# 1_P1_schdoc.net
KiCad netlist of a schematic drawn in Altium Designer
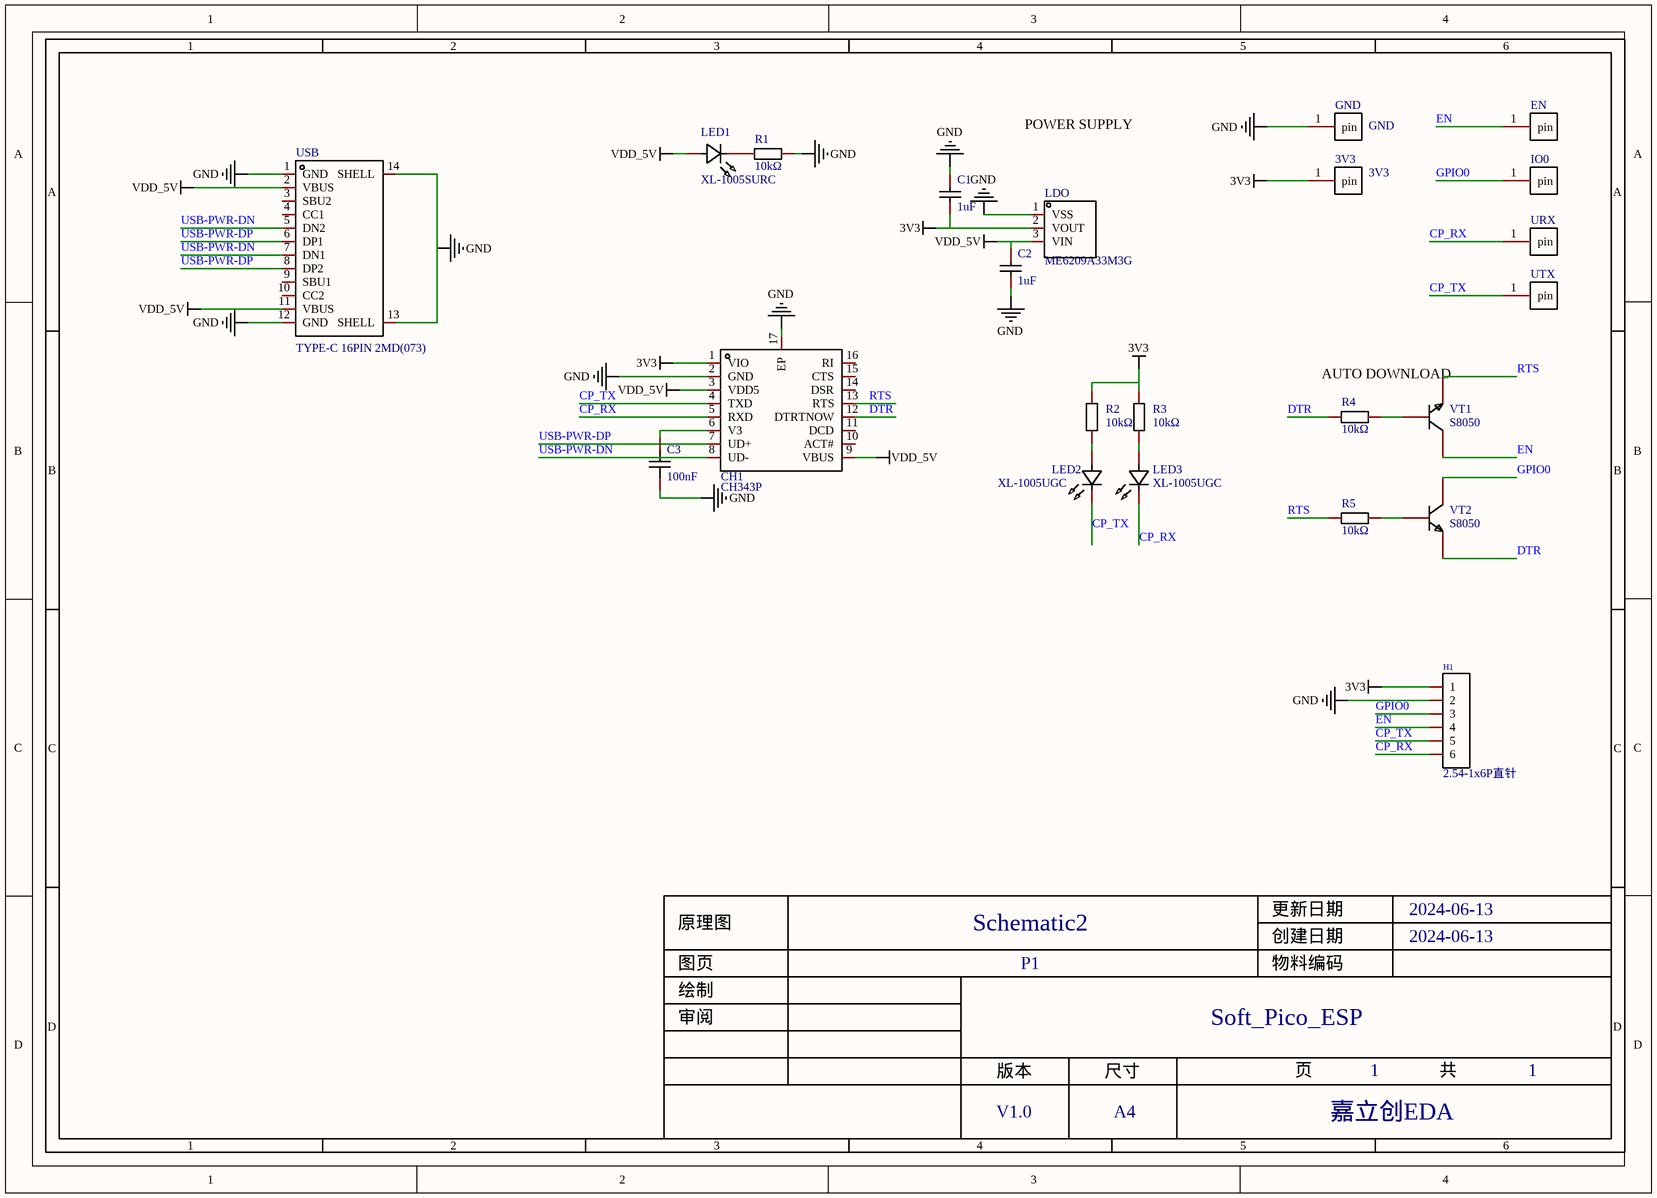
[diagram p0: 1_P1.schdoc.schdoc]

(export (version "E")
  (design (tool "Eeschema 10.0.6"))
  (components
    (comp (ref "3V3")
      (value "3V3")
      (fields (field (name "NAME") "3V3"))
      (libsource (lib "altium-import") (part "root_0_FPCB焊脚_"))
    )
    (comp (ref "C1")
      (value "1uF")
      (fields
        (field (name "MANUFACTURER") "SAMSUNG(三星)")
        (field (name "MANUFACTURER PART") "CL05A105KP5NNNC")
        (field (name "TOLERANCE") "±10%")
      )
      (libsource (lib "altium-import") (part "root_1_CL05A105KP5NNNC_"))
    )
    (comp (ref "C2")
      (value "1uF")
      (fields
        (field (name "MANUFACTURER") "SAMSUNG(三星)")
        (field (name "MANUFACTURER PART") "CL05A105KP5NNNC")
        (field (name "TOLERANCE") "±10%")
      )
      (libsource (lib "altium-import") (part "root_1_CL05A105KP5NNNC_"))
    )
    (comp (ref "C3")
      (value "100nF")
      (fields
        (field (name "MANUFACTURER") "YAGEO(国巨)")
        (field (name "MANUFACTURER PART") "CC0402KRX7R7BB104")
        (field (name "TOLERANCE") "±10%")
      )
      (libsource (lib "altium-import") (part "root_1_CC0402KRX7R7BB104_"))
    )
    (comp (ref "CH1")
      (value "CH343P")
      (description "应用功能:-;接口协议:-;")
      (fields (field (name "NAME") "CH343P") (field (name "MANUFACTURER") "WCH(南京沁恒)"))
      (libsource (lib "altium-import") (part "root_0_CH343P_"))
    )
    (comp (ref "EN") (value "FPCB焊脚") (libsource (lib "altium-import") (part "root_0_FPCB焊脚_")))
    (comp (ref "GND")
      (value "GND")
      (fields (field (name "NAME") "GND"))
      (libsource (lib "altium-import") (part "root_0_FPCB焊脚_"))
    )
    (comp (ref "H1")
      (value "2.54-1x6P直针")
      (fields (field (name "NAME") "2.54-1x6P直针") (field (name "MANUFACTURER") "BOOMELE(博穆精密)"))
      (libsource (lib "altium-import") (part "root_0_2.54-1x6P直针_"))
    )
    (comp (ref "IO0") (value "FPCB焊脚") (libsource (lib "altium-import") (part "root_0_FPCB焊脚_")))
    (comp (ref "LDO")
      (value "ME6209A33M3G")
      (description "输出类型:固定;最大输入电压:18V;输出电压:3.3V;最大输出电流:250mA;电源纹波抑制比(PSRR):-;输出极性:正极;")
      (fields (field (name "NAME") "ME6209A33M3G") (field (name "MANUFACTURER") "MICRONE(南京微盟)"))
      (libsource (lib "altium-import") (part "root_0_ME6209A33M3G_"))
    )
    (comp (ref "LED1")
      (value "XL-1005SURC")
      (description "发光颜色:红色;功率:55mW;正向电流:25mA;主波长:620nm;透镜颜色:无色透明透镜;色温:6000K~7000K;发光角度:120°;载带方式:正贴;工作温度:-30℃~+85℃;")
      (fields (field (name "NAME") "XL-1005SURC") (field (name "MANUFACTURER") "XINGLIGHT(成兴光)"))
      (libsource (lib "altium-import") (part "root_2_XL-1005SURC_"))
    )
    (comp (ref "LED2")
      (value "XL-1005UGC")
      (description "发光颜色:翠绿色;功率:80mW;正向电流:25mA;主波长:516nm;透镜颜色:无色透明透镜;色温:-;发光角度:120°;载带方式:正贴;工作温度:-30℃~+85℃;")
      (fields (field (name "NAME") "XL-1005UGC") (field (name "MANUFACTURER") "XINGLIGHT(成兴光)"))
      (libsource (lib "altium-import") (part "root_1_XL-1005UGC_"))
    )
    (comp (ref "LED3")
      (value "XL-1005UGC")
      (description "发光颜色:翠绿色;功率:80mW;正向电流:25mA;主波长:516nm;透镜颜色:无色透明透镜;色温:-;发光角度:120°;载带方式:正贴;工作温度:-30℃~+85℃;")
      (fields (field (name "NAME") "XL-1005UGC") (field (name "MANUFACTURER") "XINGLIGHT(成兴光)"))
      (libsource (lib "altium-import") (part "root_1_XL-1005UGC_"))
    )
    (comp (ref "R1")
      (value "10kΩ")
      (description "电阻类型:薄膜电阻;阻值:10kΩ;精度:±0.5%;功率:63mW;温度系数:±25ppm/;最大工作电压:25V;工作温度范围:-55~+155;")
      (fields
        (field (name "MANUFACTURER") "EVER OHMS(天二科技)")
        (field (name "MANUFACTURER PART") "TR0402D10K0Q1025Z")
      )
      (libsource (lib "altium-import") (part "root_2_TR0402D10K0Q1025Z_"))
    )
    (comp (ref "R2")
      (value "10kΩ")
      (description "电阻类型:薄膜电阻;阻值:10kΩ;精度:±0.5%;功率:63mW;温度系数:±25ppm/;最大工作电压:25V;工作温度范围:-55~+155;")
      (fields
        (field (name "MANUFACTURER") "EVER OHMS(天二科技)")
        (field (name "MANUFACTURER PART") "TR0402D10K0Q1025Z")
      )
      (libsource (lib "altium-import") (part "root_3_TR0402D10K0Q1025Z_"))
    )
    (comp (ref "R3")
      (value "10kΩ")
      (description "电阻类型:薄膜电阻;阻值:10kΩ;精度:±0.5%;功率:63mW;温度系数:±25ppm/;最大工作电压:25V;工作温度范围:-55~+155;")
      (fields
        (field (name "MANUFACTURER") "EVER OHMS(天二科技)")
        (field (name "MANUFACTURER PART") "TR0402D10K0Q1025Z")
      )
      (libsource (lib "altium-import") (part "root_3_TR0402D10K0Q1025Z_"))
    )
    (comp (ref "R4")
      (value "10kΩ")
      (description "电阻类型:薄膜电阻;阻值:10kΩ;精度:±0.5%;功率:63mW;温度系数:±25ppm/;最大工作电压:25V;工作温度范围:-55~+155;")
      (fields
        (field (name "MANUFACTURER") "EVER OHMS(天二科技)")
        (field (name "MANUFACTURER PART") "TR0402D10K0Q1025Z")
      )
      (libsource (lib "altium-import") (part "root_0_TR0402D10K0Q1025Z_"))
    )
    (comp (ref "R5")
      (value "10kΩ")
      (description "电阻类型:薄膜电阻;阻值:10kΩ;精度:±0.5%;功率:63mW;温度系数:±25ppm/;最大工作电压:25V;工作温度范围:-55~+155;")
      (fields
        (field (name "MANUFACTURER") "EVER OHMS(天二科技)")
        (field (name "MANUFACTURER PART") "TR0402D10K0Q1025Z")
      )
      (libsource (lib "altium-import") (part "root_0_TR0402D10K0Q1025Z_"))
    )
    (comp (ref "URX") (value "FPCB焊脚") (libsource (lib "altium-import") (part "root_0_FPCB焊脚_")))
    (comp (ref "USB")
      (value "TYPE-C 16PIN 2MD(073)")
      (description "连接器类型:Type-C;标准:-;公母:母;端口数量:1;触点数量:16P;安装方式:卧贴;额定电流 - 电源:5A;工作温度范围:-25℃~+85℃;")
      (fields (field (name "DEVICE") "TYPE-C 16PIN 2MD(073)") (field (name "MANUFACTURER") "SHOU HAN(首韩)"))
      (libsource (lib "altium-import") (part "root_0_TYPE-C 16PIN 2MD(073)_"))
    )
    (comp (ref "UTX") (value "FPCB焊脚") (libsource (lib "altium-import") (part "root_0_FPCB焊脚_")))
    (comp (ref "VT1")
      (value "S8050")
      (description "Surface mount NPN transistor, package SOT-23")
      (fields (field (name "NAME") "S8050"))
      (libsource (lib "altium-import") (part "root_2_mirrored_S8050_"))
    )
    (comp (ref "VT2")
      (value "S8050")
      (description "Surface mount NPN transistor, package SOT-23")
      (fields (field (name "NAME") "S8050"))
      (libsource (lib "altium-import") (part "root_0_S8050_"))
    )
  )
  (nets
    (net (code "1") (name "/CP_RX") (class "Default")
      (node (ref "CH1") (pin "5") (pinfunction "RXD_5") (pintype "passive"))
      (node (ref "H1") (pin "6") (pinfunction "6_6") (pintype "passive"))
      (node (ref "LED3") (pin "1") (pinfunction "K_1") (pintype "passive"))
      (node (ref "URX") (pin "1") (pinfunction "pin_1") (pintype "passive"))
    )
    (net (code "2") (name "/CP_TX") (class "Default")
      (node (ref "CH1") (pin "4") (pinfunction "TXD_4") (pintype "passive"))
      (node (ref "H1") (pin "5") (pinfunction "5_5") (pintype "passive"))
      (node (ref "LED2") (pin "1") (pinfunction "K_1") (pintype "passive"))
      (node (ref "UTX") (pin "1") (pinfunction "pin_1") (pintype "passive"))
    )
    (net (code "3") (name "/DTR") (class "Default")
      (node (ref "CH1") (pin "12") (pinfunction "DTRTNOW_12") (pintype "passive"))
      (node (ref "R4") (pin "1") (pinfunction "1_1") (pintype "passive"))
      (node (ref "VT2") (pin "2") (pinfunction "E_2") (pintype "passive"))
    )
    (net (code "4") (name "/EN") (class "Default")
      (node (ref "EN") (pin "1") (pinfunction "pin_1") (pintype "passive"))
      (node (ref "H1") (pin "4") (pinfunction "4_4") (pintype "passive"))
      (node (ref "VT1") (pin "3") (pinfunction "C_3") (pintype "passive"))
    )
    (net (code "5") (name "/GPIO0") (class "Default")
      (node (ref "H1") (pin "3") (pinfunction "3_3") (pintype "passive"))
      (node (ref "IO0") (pin "1") (pinfunction "pin_1") (pintype "passive"))
      (node (ref "VT2") (pin "3") (pinfunction "C_3") (pintype "passive"))
    )
    (net (code "6") (name "/RTS") (class "Default")
      (node (ref "CH1") (pin "13") (pinfunction "RTS_13") (pintype "passive"))
      (node (ref "R5") (pin "1") (pinfunction "1_1") (pintype "passive"))
      (node (ref "VT1") (pin "2") (pinfunction "E_2") (pintype "passive"))
    )
    (net (code "7") (name "/USB-PWR-DN") (class "Default")
      (node (ref "CH1") (pin "8") (pinfunction "UD-_8") (pintype "passive"))
      (node (ref "USB") (pin "5") (pinfunction "DN2_5") (pintype "passive"))
      (node (ref "USB") (pin "7") (pinfunction "DN1_7") (pintype "passive"))
    )
    (net (code "8") (name "/USB-PWR-DP") (class "Default")
      (node (ref "CH1") (pin "7") (pinfunction "UD+_7") (pintype "passive"))
      (node (ref "USB") (pin "6") (pinfunction "DP1_6") (pintype "passive"))
      (node (ref "USB") (pin "8") (pinfunction "DP2_8") (pintype "passive"))
    )
    (net (code "9") (name "3V3") (class "Default")
      (node (ref "3V3") (pin "1") (pinfunction "pin_1") (pintype "passive"))
      (node (ref "C1") (pin "1") (pinfunction "1_1") (pintype "passive"))
      (node (ref "CH1") (pin "1") (pinfunction "VIO_1") (pintype "passive"))
      (node (ref "H1") (pin "1") (pinfunction "1_1") (pintype "passive"))
      (node (ref "LDO") (pin "2") (pinfunction "VOUT_2") (pintype "passive"))
      (node (ref "R2") (pin "1") (pinfunction "1_1") (pintype "passive"))
      (node (ref "R3") (pin "1") (pinfunction "1_1") (pintype "passive"))
    )
    (net (code "10") (name "GND") (class "Default")
      (node (ref "C1") (pin "2") (pinfunction "2_2") (pintype "passive"))
      (node (ref "C2") (pin "1") (pinfunction "1_1") (pintype "passive"))
      (node (ref "C3") (pin "1") (pinfunction "1_1") (pintype "passive"))
      (node (ref "CH1") (pin "17") (pinfunction "EP_17") (pintype "passive"))
      (node (ref "CH1") (pin "2") (pinfunction "GND_2") (pintype "passive"))
      (node (ref "GND") (pin "1") (pinfunction "pin_1") (pintype "passive"))
      (node (ref "H1") (pin "2") (pinfunction "2_2") (pintype "passive"))
      (node (ref "LDO") (pin "1") (pinfunction "VSS_1") (pintype "passive"))
      (node (ref "R1") (pin "1") (pinfunction "1_1") (pintype "passive"))
      (node (ref "USB") (pin "1") (pinfunction "GND_1") (pintype "passive"))
      (node (ref "USB") (pin "12") (pinfunction "GND_12") (pintype "passive"))
      (node (ref "USB") (pin "13") (pinfunction "SHELL_13") (pintype "passive"))
      (node (ref "USB") (pin "14") (pinfunction "SHELL_14") (pintype "passive"))
    )
    (net (code "11") (name "Net-(CH1-V3)") (class "Default")
      (node (ref "C3") (pin "2") (pinfunction "2_2") (pintype "passive"))
      (node (ref "CH1") (pin "6") (pinfunction "V3_6") (pintype "passive"))
    )
    (net (code "12") (name "Net-(LED1-A)") (class "Default")
      (node (ref "LED1") (pin "2") (pinfunction "A_2") (pintype "passive"))
      (node (ref "R1") (pin "2") (pinfunction "2_2") (pintype "passive"))
    )
    (net (code "13") (name "Net-(LED2-A)") (class "Default")
      (node (ref "LED2") (pin "2") (pinfunction "A_2") (pintype "passive"))
      (node (ref "R2") (pin "2") (pinfunction "2_2") (pintype "passive"))
    )
    (net (code "14") (name "Net-(LED3-A)") (class "Default")
      (node (ref "LED3") (pin "2") (pinfunction "A_2") (pintype "passive"))
      (node (ref "R3") (pin "2") (pinfunction "2_2") (pintype "passive"))
    )
    (net (code "15") (name "Net-(VT1-B)") (class "Default")
      (node (ref "R4") (pin "2") (pinfunction "2_2") (pintype "passive"))
      (node (ref "VT1") (pin "1") (pinfunction "B_1") (pintype "passive"))
    )
    (net (code "16") (name "Net-(VT2-B)") (class "Default")
      (node (ref "R5") (pin "2") (pinfunction "2_2") (pintype "passive"))
      (node (ref "VT2") (pin "1") (pinfunction "B_1") (pintype "passive"))
    )
    (net (code "17") (name "VDD_5V") (class "Default")
      (node (ref "C2") (pin "2") (pinfunction "2_2") (pintype "passive"))
      (node (ref "CH1") (pin "3") (pinfunction "VDD5_3") (pintype "passive"))
      (node (ref "CH1") (pin "9") (pinfunction "VBUS_9") (pintype "passive"))
      (node (ref "LDO") (pin "3") (pinfunction "VIN_3") (pintype "passive"))
      (node (ref "LED1") (pin "1") (pinfunction "K_1") (pintype "passive"))
      (node (ref "USB") (pin "11") (pinfunction "VBUS_11") (pintype "passive"))
      (node (ref "USB") (pin "2") (pinfunction "VBUS_2") (pintype "passive"))
    )
    (net (code "18") (name "unconnected-(CH1-ACT#-Pad10)") (class "Default")
      (node (ref "CH1") (pin "10") (pinfunction "ACT#_10") (pintype "passive"))
    )
    (net (code "19") (name "unconnected-(CH1-CTS-Pad15)") (class "Default")
      (node (ref "CH1") (pin "15") (pinfunction "CTS_15") (pintype "passive"))
    )
    (net (code "20") (name "unconnected-(CH1-DCD-Pad11)") (class "Default")
      (node (ref "CH1") (pin "11") (pinfunction "DCD_11") (pintype "passive"))
    )
    (net (code "21") (name "unconnected-(CH1-DSR-Pad14)") (class "Default")
      (node (ref "CH1") (pin "14") (pinfunction "DSR_14") (pintype "passive"))
    )
    (net (code "22") (name "unconnected-(CH1-RI-Pad16)") (class "Default")
      (node (ref "CH1") (pin "16") (pinfunction "RI_16") (pintype "passive"))
    )
    (net (code "23") (name "unconnected-(USB-CC1-Pad4)") (class "Default")
      (node (ref "USB") (pin "4") (pinfunction "CC1_4") (pintype "passive"))
    )
    (net (code "24") (name "unconnected-(USB-CC2-Pad10)") (class "Default")
      (node (ref "USB") (pin "10") (pinfunction "CC2_10") (pintype "passive"))
    )
    (net (code "25") (name "unconnected-(USB-SBU1-Pad9)") (class "Default")
      (node (ref "USB") (pin "9") (pinfunction "SBU1_9") (pintype "passive"))
    )
    (net (code "26") (name "unconnected-(USB-SBU2-Pad3)") (class "Default")
      (node (ref "USB") (pin "3") (pinfunction "SBU2_3") (pintype "passive"))
    )
  )
)
